# LSM9DS0.net
KiCad netlist of a schematic drawn in Altium Designer
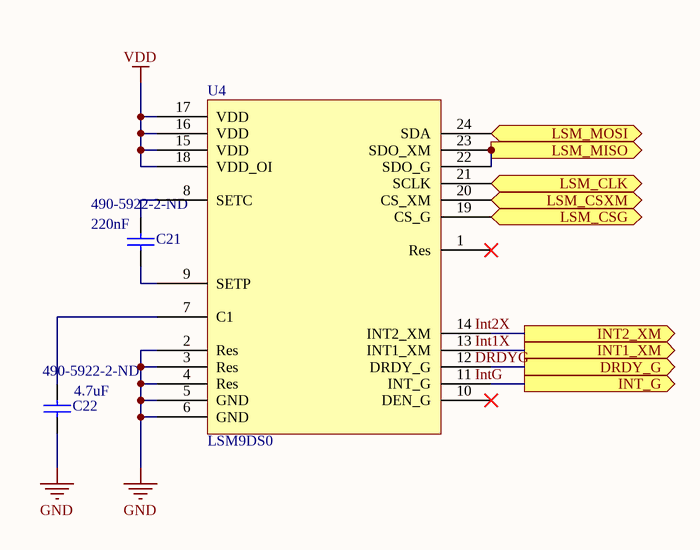
[diagram p0: LSM9DS0.SchDoc]

(export (version "E")
  (design (tool "Eeschema 10.0.6"))
  (components
    (comp (ref "C21")
      (value "220nF")
      (footprint "0402")
      (description "Capacitor (Semiconductor SIM Model)")
      (fields
        (field (name "SUPPLIER PART NUMBER 1") "490-5922-2-ND")
        (field (name "Comment") "Cap Semi")
        (field (name "PUBLISHER") "Altium Limited")
      )
      (libsource (lib "Miscellaneous Devices") (part "Cap Semi"))
    )
    (comp (ref "C22")
      (value "4.7uF")
      (footprint "0402")
      (description "Capacitor (Semiconductor SIM Model)")
      (fields
        (field (name "SUPPLIER PART NUMBER 1") "490-5922-2-ND")
        (field (name "Comment") "Cap Semi")
        (field (name "PUBLISHER") "Altium Limited")
      )
      (libsource (lib "Miscellaneous Devices") (part "Cap Semi"))
    )
    (comp (ref "U4")
      (value "Component_1")
      (footprint "PCBComponent_1")
      (libsource (lib "LSM9DS0") (part "Component_1"))
    )
  )
  (nets
    (net (code "2") (name "/DRDY_G") (class "Default")
      (node (ref "U4") (pin "12") (pinfunction "DRDY_G_12") (pintype "passive"))
    )
    (net (code "3") (name "/INT1_XM") (class "Default")
      (node (ref "U4") (pin "13") (pinfunction "INT1_XM_13") (pintype "passive"))
    )
    (net (code "4") (name "/INT2_XM") (class "Default")
      (node (ref "U4") (pin "14") (pinfunction "INT2_XM_14") (pintype "passive"))
    )
    (net (code "5") (name "/INT_G") (class "Default")
      (node (ref "U4") (pin "11") (pinfunction "INT_G_11") (pintype "passive"))
    )
    (net (code "9") (name "/LSM_CLK") (class "Default")
      (node (ref "U4") (pin "21") (pinfunction "SCLK_21") (pintype "passive"))
    )
    (net (code "10") (name "/LSM_CSG") (class "Default")
      (node (ref "U4") (pin "19") (pinfunction "CS_G_19") (pintype "passive"))
    )
    (net (code "11") (name "/LSM_CSXM") (class "Default")
      (node (ref "U4") (pin "20") (pinfunction "CS_XM_20") (pintype "passive"))
    )
    (net (code "12") (name "/LSM_MISO") (class "Default")
      (node (ref "U4") (pin "22") (pinfunction "SDO_G_22") (pintype "passive"))
      (node (ref "U4") (pin "23") (pinfunction "SDO_XM_23") (pintype "passive"))
    )
    (net (code "13") (name "/LSM_MOSI") (class "Default")
      (node (ref "U4") (pin "24") (pinfunction "SDA_24") (pintype "passive"))
    )
    (net (code "14") (name "GND") (class "Default")
      (node (ref "C22") (pin "1") (pinfunction "1_1") (pintype "passive"))
      (node (ref "U4") (pin "2") (pinfunction "Res_2") (pintype "passive"))
      (node (ref "U4") (pin "3") (pinfunction "Res_3") (pintype "passive"))
      (node (ref "U4") (pin "4") (pinfunction "Res_4") (pintype "passive"))
      (node (ref "U4") (pin "5") (pinfunction "GND_5") (pintype "passive"))
      (node (ref "U4") (pin "6") (pinfunction "GND_6") (pintype "passive"))
    )
    (net (code "15") (name "Net-(U4-C1)") (class "Default")
      (node (ref "C22") (pin "2") (pinfunction "2_2") (pintype "passive"))
      (node (ref "U4") (pin "7") (pinfunction "C1_7") (pintype "passive"))
    )
    (net (code "16") (name "Net-(U4-SETC)") (class "Default")
      (node (ref "C21") (pin "2") (pinfunction "2_2") (pintype "passive"))
      (node (ref "U4") (pin "8") (pinfunction "SETC_8") (pintype "passive"))
    )
    (net (code "17") (name "Net-(U4-SETP)") (class "Default")
      (node (ref "C21") (pin "1") (pinfunction "1_1") (pintype "passive"))
      (node (ref "U4") (pin "9") (pinfunction "SETP_9") (pintype "passive"))
    )
    (net (code "18") (name "VDD") (class "Default")
      (node (ref "U4") (pin "15") (pinfunction "VDD_15") (pintype "passive"))
      (node (ref "U4") (pin "16") (pinfunction "VDD_16") (pintype "passive"))
      (node (ref "U4") (pin "17") (pinfunction "VDD_17") (pintype "passive"))
      (node (ref "U4") (pin "18") (pinfunction "VDD_OI_18") (pintype "passive"))
    )
    (net (code "19") (name "unconnected-(U4-DEN_G-Pad10)") (class "Default")
      (node (ref "U4") (pin "10") (pinfunction "DEN_G_10") (pintype "passive+no_connect"))
    )
    (net (code "20") (name "unconnected-(U4-Res-Pad1)") (class "Default")
      (node (ref "U4") (pin "1") (pinfunction "Res_1") (pintype "passive+no_connect"))
    )
  )
)
